# Training_Board.net
KiCad netlist of a schematic drawn in EAGLE
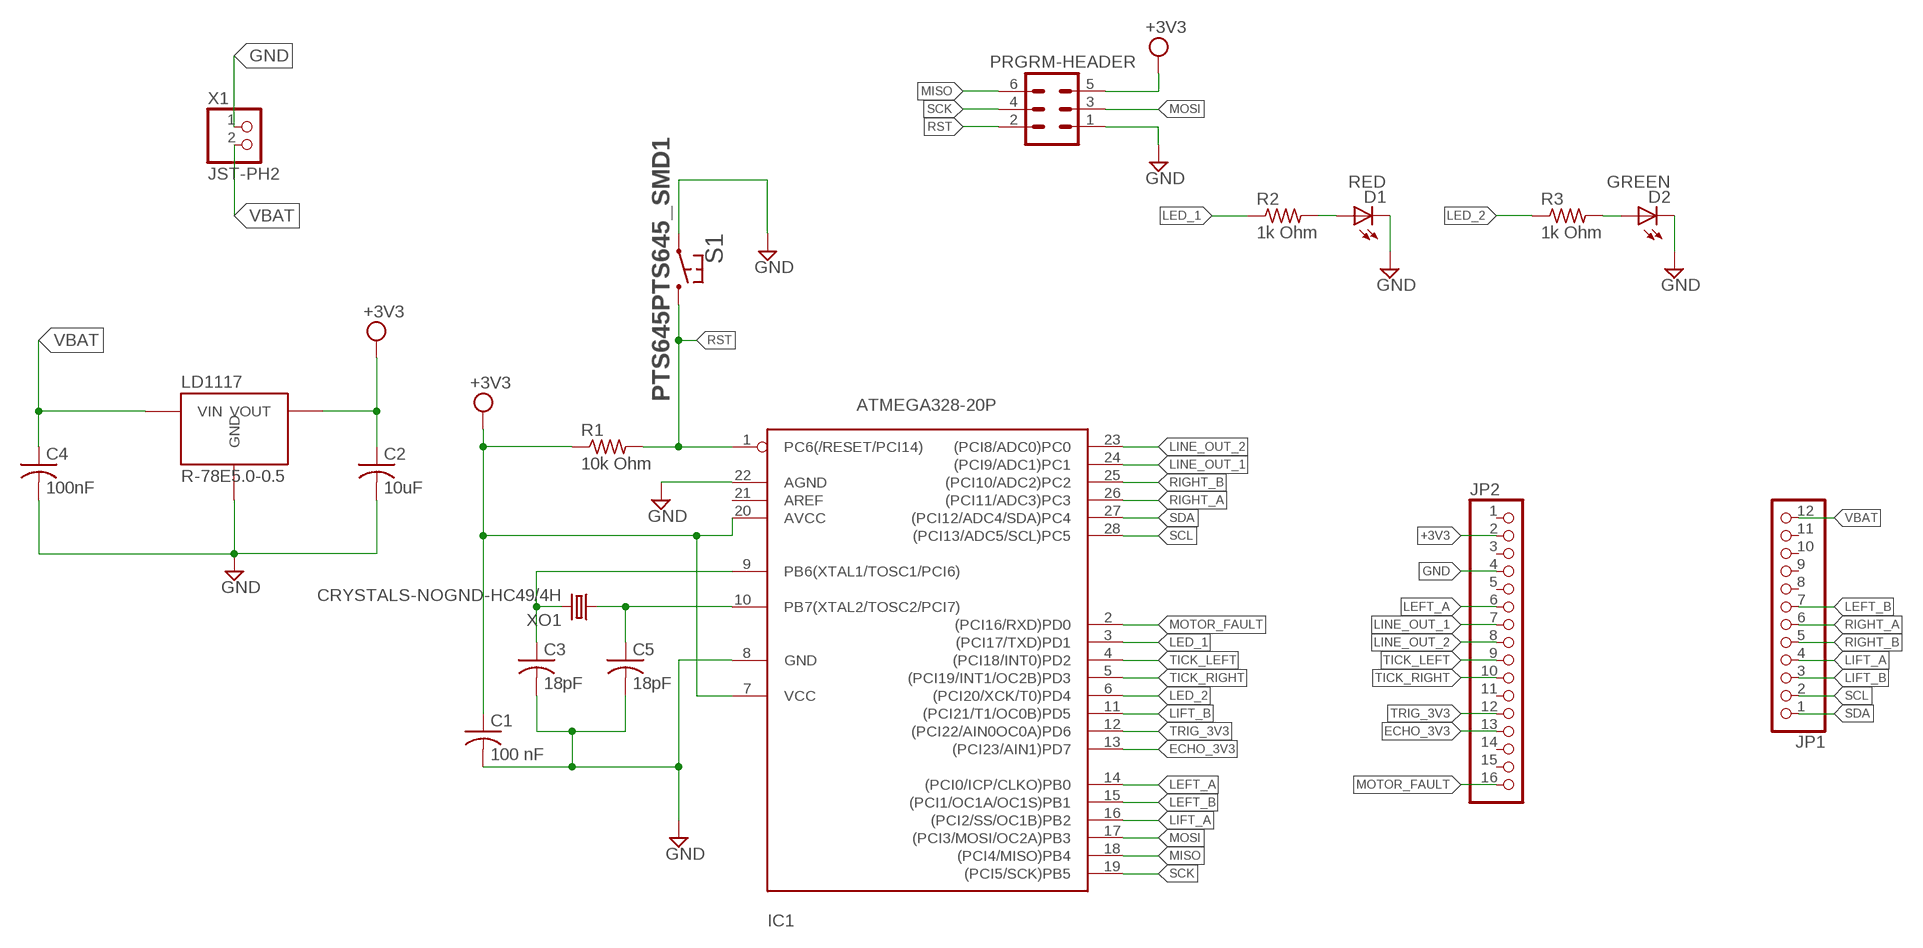
[diagram p0: schematic, sheet 1]

(export (version "E")
  (design (tool "Eeschema 10.0.6"))
  (components
    (comp (ref "C1")
      (value "100 nF")
      (footprint "eagle-import:C0603")
      (libsource (lib "eagle-import") (part "resistor_348_C-USC0603"))
    )
    (comp (ref "C2")
      (value "10uF")
      (footprint "eagle-import:C0603")
      (libsource (lib "eagle-import") (part "C-USC0603"))
    )
    (comp (ref "C3")
      (value "18pF")
      (footprint "eagle-import:C0603")
      (libsource (lib "eagle-import") (part "resistor_348_C-USC0603"))
    )
    (comp (ref "C4")
      (value "100nF")
      (footprint "eagle-import:C0603")
      (libsource (lib "eagle-import") (part "C-USC0603"))
    )
    (comp (ref "C5")
      (value "18pF")
      (footprint "eagle-import:C0603")
      (libsource (lib "eagle-import") (part "resistor_348_C-USC0603"))
    )
    (comp (ref "D1")
      (value "RED")
      (footprint "eagle-import:CHIP-LED0603")
      (libsource (lib "eagle-import") (part "LEDCHIP-LED0603"))
    )
    (comp (ref "D2")
      (value "GREEN")
      (footprint "eagle-import:CHIP-LED0603")
      (libsource (lib "eagle-import") (part "LEDCHIP-LED0603"))
    )
    (comp (ref "IC1")
      (value "ATMEGA328-20P")
      (footprint "eagle-import:DIL28-3")
      (libsource (lib "eagle-import") (part "ATMEGA328P-20"))
    )
    (comp (ref "JP1")
      (value "PINHD-1X12")
      (footprint "eagle-import:1X12")
      (libsource (lib "eagle-import") (part "PINHD-1X12"))
    )
    (comp (ref "JP2")
      (value "PINHD-1X16")
      (footprint "eagle-import:1X16")
      (libsource (lib "eagle-import") (part "PINHD-1X16"))
    )
    (comp (ref "LD1117")
      (value "R-78E5.0-0.5")
      (footprint "eagle-import:R-78E")
      (libsource (lib "eagle-import") (part "R-78E5.0-0.5"))
    )
    (comp (ref "PRGRM-HEADER")
      (value "MA03-2")
      (footprint "eagle-import:MA03-2")
      (libsource (lib "eagle-import") (part "MA03-2"))
    )
    (comp (ref "R1")
      (value "10k Ohm")
      (footprint "eagle-import:R0603")
      (libsource (lib "eagle-import") (part "resistor_348_R-US_R0603"))
    )
    (comp (ref "R2")
      (value "1k Ohm")
      (footprint "eagle-import:M0805")
      (libsource (lib "eagle-import") (part "R-US_M0805"))
    )
    (comp (ref "R3")
      (value "1k Ohm")
      (footprint "eagle-import:M0805")
      (libsource (lib "eagle-import") (part "R-US_M0805"))
    )
    (comp (ref "S1")
      (value "PTS645PTS645_SMD1")
      (footprint "eagle-import:PTS645_SMD")
      (libsource (lib "eagle-import") (part "PTS645PTS645_SMD1"))
    )
    (comp (ref "X1")
      (value "JST-PH2")
      (footprint "eagle-import:JST-PH")
      (libsource (lib "eagle-import") (part "JST-PH2"))
    )
    (comp (ref "XO1")
      (value "CRYSTALS-NOGND-HC49/4H")
      (footprint "eagle-import:HC49")
      (libsource (lib "eagle-import") (part "CRYSTALS-NOGND-HC49/4H"))
    )
  )
  (nets
    (net (code "1") (name "+3V3") (class "Default")
      (node (ref "C1") (pin "1") (pinfunction "1_1") (pintype "passive"))
      (node (ref "C2") (pin "1") (pinfunction "1_1") (pintype "passive"))
      (node (ref "IC1") (pin "20") (pinfunction "AVCC_20") (pintype "bidirectional"))
      (node (ref "IC1") (pin "7") (pinfunction "VCC_7") (pintype "bidirectional"))
      (node (ref "JP2") (pin "2") (pinfunction "2_2") (pintype "passive"))
      (node (ref "LD1117") (pin "3") (pinfunction "VOUT_3") (pintype "bidirectional"))
      (node (ref "PRGRM-HEADER") (pin "5") (pinfunction "5_5") (pintype "passive"))
      (node (ref "R1") (pin "1") (pinfunction "1_1") (pintype "passive"))
    )
    (net (code "2") (name "ECHO_3V3") (class "Default")
      (node (ref "IC1") (pin "13") (pinfunction "(PCI23/AIN1)PD7_13") (pintype "bidirectional"))
      (node (ref "JP2") (pin "13") (pinfunction "13_13") (pintype "passive"))
    )
    (net (code "3") (name "GND") (class "Default")
      (node (ref "C1") (pin "2") (pinfunction "2_2") (pintype "passive"))
      (node (ref "C2") (pin "2") (pinfunction "2_2") (pintype "passive"))
      (node (ref "C3") (pin "2") (pinfunction "2_2") (pintype "passive"))
      (node (ref "C4") (pin "2") (pinfunction "2_2") (pintype "passive"))
      (node (ref "C5") (pin "2") (pinfunction "2_2") (pintype "passive"))
      (node (ref "D1") (pin "C") (pinfunction "C_C") (pintype "passive"))
      (node (ref "D2") (pin "C") (pinfunction "C_C") (pintype "passive"))
      (node (ref "IC1") (pin "22") (pinfunction "AGND_22") (pintype "bidirectional"))
      (node (ref "IC1") (pin "8") (pinfunction "GND_8") (pintype "bidirectional"))
      (node (ref "JP2") (pin "4") (pinfunction "4_4") (pintype "passive"))
      (node (ref "LD1117") (pin "2") (pinfunction "GND_2") (pintype "bidirectional"))
      (node (ref "PRGRM-HEADER") (pin "1") (pinfunction "1_1") (pintype "passive"))
      (node (ref "S1") (pin "P$1") (pinfunction "1_P$1") (pintype "passive"))
      (node (ref "S1") (pin "P$2") (pinfunction "1_P$2") (pintype "passive"))
      (node (ref "X1") (pin "1") (pinfunction "1_1") (pintype "passive"))
    )
    (net (code "4") (name "LED_1") (class "Default")
      (node (ref "IC1") (pin "3") (pinfunction "(PCI17/TXD)PD1_3") (pintype "bidirectional"))
      (node (ref "R2") (pin "1") (pinfunction "1_1") (pintype "passive"))
    )
    (net (code "5") (name "LED_2") (class "Default")
      (node (ref "IC1") (pin "6") (pinfunction "(PCI20/XCK/T0)PD4_6") (pintype "bidirectional"))
      (node (ref "R3") (pin "1") (pinfunction "1_1") (pintype "passive"))
    )
    (net (code "6") (name "LEFT_A") (class "Default")
      (node (ref "IC1") (pin "14") (pinfunction "(PCI0/ICP/CLKO)PB0_14") (pintype "bidirectional"))
      (node (ref "JP2") (pin "6") (pinfunction "6_6") (pintype "passive"))
    )
    (net (code "7") (name "LEFT_B") (class "Default")
      (node (ref "IC1") (pin "15") (pinfunction "(PCI1/OC1A/OC1S)PB1_15") (pintype "bidirectional"))
      (node (ref "JP1") (pin "7") (pinfunction "7_7") (pintype "passive"))
    )
    (net (code "8") (name "LIFT_A") (class "Default")
      (node (ref "IC1") (pin "16") (pinfunction "(PCI2/SS/OC1B)PB2_16") (pintype "bidirectional"))
      (node (ref "JP1") (pin "4") (pinfunction "4_4") (pintype "passive"))
    )
    (net (code "9") (name "LIFT_B") (class "Default")
      (node (ref "IC1") (pin "11") (pinfunction "(PCI21/T1/OC0B)PD5_11") (pintype "bidirectional"))
      (node (ref "JP1") (pin "3") (pinfunction "3_3") (pintype "passive"))
    )
    (net (code "10") (name "LINE_OUT_1") (class "Default")
      (node (ref "IC1") (pin "24") (pinfunction "(PCI9/ADC1)PC1_24") (pintype "bidirectional"))
      (node (ref "JP2") (pin "7") (pinfunction "7_7") (pintype "passive"))
    )
    (net (code "11") (name "LINE_OUT_2") (class "Default")
      (node (ref "IC1") (pin "23") (pinfunction "(PCI8/ADC0)PC0_23") (pintype "bidirectional"))
      (node (ref "JP2") (pin "8") (pinfunction "8_8") (pintype "passive"))
    )
    (net (code "12") (name "MISO") (class "Default")
      (node (ref "IC1") (pin "18") (pinfunction "(PCI4/MISO)PB4_18") (pintype "bidirectional"))
      (node (ref "PRGRM-HEADER") (pin "6") (pinfunction "6_6") (pintype "passive"))
    )
    (net (code "13") (name "MOSI") (class "Default")
      (node (ref "IC1") (pin "17") (pinfunction "(PCI3/MOSI/OC2A)PB3_17") (pintype "bidirectional"))
      (node (ref "PRGRM-HEADER") (pin "3") (pinfunction "3_3") (pintype "passive"))
    )
    (net (code "14") (name "MOTOR_FAULT") (class "Default")
      (node (ref "IC1") (pin "2") (pinfunction "(PCI16/RXD)PD0_2") (pintype "bidirectional"))
      (node (ref "JP2") (pin "16") (pinfunction "16_16") (pintype "passive"))
    )
    (net (code "15") (name "Net-(D1-PadA)") (class "Default")
      (node (ref "D1") (pin "A") (pinfunction "A_A") (pintype "passive"))
      (node (ref "R2") (pin "2") (pinfunction "2_2") (pintype "passive"))
    )
    (net (code "16") (name "Net-(D2-PadA)") (class "Default")
      (node (ref "D2") (pin "A") (pinfunction "A_A") (pintype "passive"))
      (node (ref "R3") (pin "2") (pinfunction "2_2") (pintype "passive"))
    )
    (net (code "17") (name "Net-(IC1-PB6(XTAL1{slash}TOSC1{slash}PCI6))") (class "Default")
      (node (ref "C3") (pin "1") (pinfunction "1_1") (pintype "passive"))
      (node (ref "IC1") (pin "9") (pinfunction "PB6(XTAL1/TOSC1/PCI6)_9") (pintype "bidirectional"))
      (node (ref "XO1") (pin "2") (pinfunction "2_2") (pintype "passive"))
    )
    (net (code "18") (name "Net-(IC1-PB7(XTAL2{slash}TOSC2{slash}PCI7))") (class "Default")
      (node (ref "C5") (pin "1") (pinfunction "1_1") (pintype "passive"))
      (node (ref "IC1") (pin "10") (pinfunction "PB7(XTAL2/TOSC2/PCI7)_10") (pintype "bidirectional"))
      (node (ref "XO1") (pin "1") (pinfunction "1_1") (pintype "passive"))
    )
    (net (code "19") (name "RIGHT_A") (class "Default")
      (node (ref "IC1") (pin "26") (pinfunction "(PCI11/ADC3)PC3_26") (pintype "bidirectional"))
      (node (ref "JP1") (pin "6") (pinfunction "6_6") (pintype "passive"))
    )
    (net (code "20") (name "RIGHT_B") (class "Default")
      (node (ref "IC1") (pin "25") (pinfunction "(PCI10/ADC2)PC2_25") (pintype "bidirectional"))
      (node (ref "JP1") (pin "5") (pinfunction "5_5") (pintype "passive"))
    )
    (net (code "21") (name "RST") (class "Default")
      (node (ref "IC1") (pin "1") (pinfunction "PC6(/RESET/PCI14)_1") (pintype "bidirectional"))
      (node (ref "PRGRM-HEADER") (pin "2") (pinfunction "2_2") (pintype "passive"))
      (node (ref "R1") (pin "2") (pinfunction "2_2") (pintype "passive"))
      (node (ref "S1") (pin "P$3") (pinfunction "2_P$3") (pintype "passive"))
      (node (ref "S1") (pin "P$4") (pinfunction "2_P$4") (pintype "passive"))
    )
    (net (code "22") (name "SCK") (class "Default")
      (node (ref "IC1") (pin "19") (pinfunction "(PCI5/SCK)PB5_19") (pintype "bidirectional"))
      (node (ref "PRGRM-HEADER") (pin "4") (pinfunction "4_4") (pintype "passive"))
    )
    (net (code "23") (name "SCL") (class "Default")
      (node (ref "IC1") (pin "28") (pinfunction "(PCI13/ADC5/SCL)PC5_28") (pintype "bidirectional"))
      (node (ref "JP1") (pin "2") (pinfunction "2_2") (pintype "passive"))
    )
    (net (code "24") (name "SDA") (class "Default")
      (node (ref "IC1") (pin "27") (pinfunction "(PCI12/ADC4/SDA)PC4_27") (pintype "bidirectional"))
      (node (ref "JP1") (pin "1") (pinfunction "1_1") (pintype "passive"))
    )
    (net (code "25") (name "TICK_LEFT") (class "Default")
      (node (ref "IC1") (pin "4") (pinfunction "(PCI18/INT0)PD2_4") (pintype "bidirectional"))
      (node (ref "JP2") (pin "9") (pinfunction "9_9") (pintype "passive"))
    )
    (net (code "26") (name "TICK_RIGHT") (class "Default")
      (node (ref "IC1") (pin "5") (pinfunction "(PCI19/INT1/OC2B)PD3_5") (pintype "bidirectional"))
      (node (ref "JP2") (pin "10") (pinfunction "10_10") (pintype "passive"))
    )
    (net (code "27") (name "TRIG_3V3") (class "Default")
      (node (ref "IC1") (pin "12") (pinfunction "(PCI22/AIN0OC0A)PD6_12") (pintype "bidirectional"))
      (node (ref "JP2") (pin "12") (pinfunction "12_12") (pintype "passive"))
    )
    (net (code "28") (name "VBAT") (class "Default")
      (node (ref "C4") (pin "1") (pinfunction "1_1") (pintype "passive"))
      (node (ref "JP1") (pin "12") (pinfunction "12_12") (pintype "passive"))
      (node (ref "LD1117") (pin "1") (pinfunction "VIN_1") (pintype "bidirectional"))
      (node (ref "X1") (pin "2") (pinfunction "2_2") (pintype "passive"))
    )
    (net (code "29") (name "unconnected-(IC1-AREF-Pad21)") (class "Default")
      (node (ref "IC1") (pin "21") (pinfunction "AREF_21") (pintype "bidirectional"))
    )
    (net (code "30") (name "unconnected-(JP1-Pad8)") (class "Default")
      (node (ref "JP1") (pin "8") (pinfunction "8_8") (pintype "passive"))
    )
    (net (code "31") (name "unconnected-(JP1-Pad9)") (class "Default")
      (node (ref "JP1") (pin "9") (pinfunction "9_9") (pintype "passive"))
    )
    (net (code "32") (name "unconnected-(JP1-Pad10)") (class "Default")
      (node (ref "JP1") (pin "10") (pinfunction "10_10") (pintype "passive"))
    )
    (net (code "33") (name "unconnected-(JP1-Pad11)") (class "Default")
      (node (ref "JP1") (pin "11") (pinfunction "11_11") (pintype "passive"))
    )
    (net (code "34") (name "unconnected-(JP2-Pad1)") (class "Default")
      (node (ref "JP2") (pin "1") (pinfunction "1_1") (pintype "passive"))
    )
    (net (code "35") (name "unconnected-(JP2-Pad3)") (class "Default")
      (node (ref "JP2") (pin "3") (pinfunction "3_3") (pintype "passive"))
    )
    (net (code "36") (name "unconnected-(JP2-Pad5)") (class "Default")
      (node (ref "JP2") (pin "5") (pinfunction "5_5") (pintype "passive"))
    )
    (net (code "37") (name "unconnected-(JP2-Pad11)") (class "Default")
      (node (ref "JP2") (pin "11") (pinfunction "11_11") (pintype "passive"))
    )
    (net (code "38") (name "unconnected-(JP2-Pad14)") (class "Default")
      (node (ref "JP2") (pin "14") (pinfunction "14_14") (pintype "passive"))
    )
    (net (code "39") (name "unconnected-(JP2-Pad15)") (class "Default")
      (node (ref "JP2") (pin "15") (pinfunction "15_15") (pintype "passive"))
    )
  )
)
